# MCU_SCH.net
KiCad netlist of a schematic drawn in Altium Designer
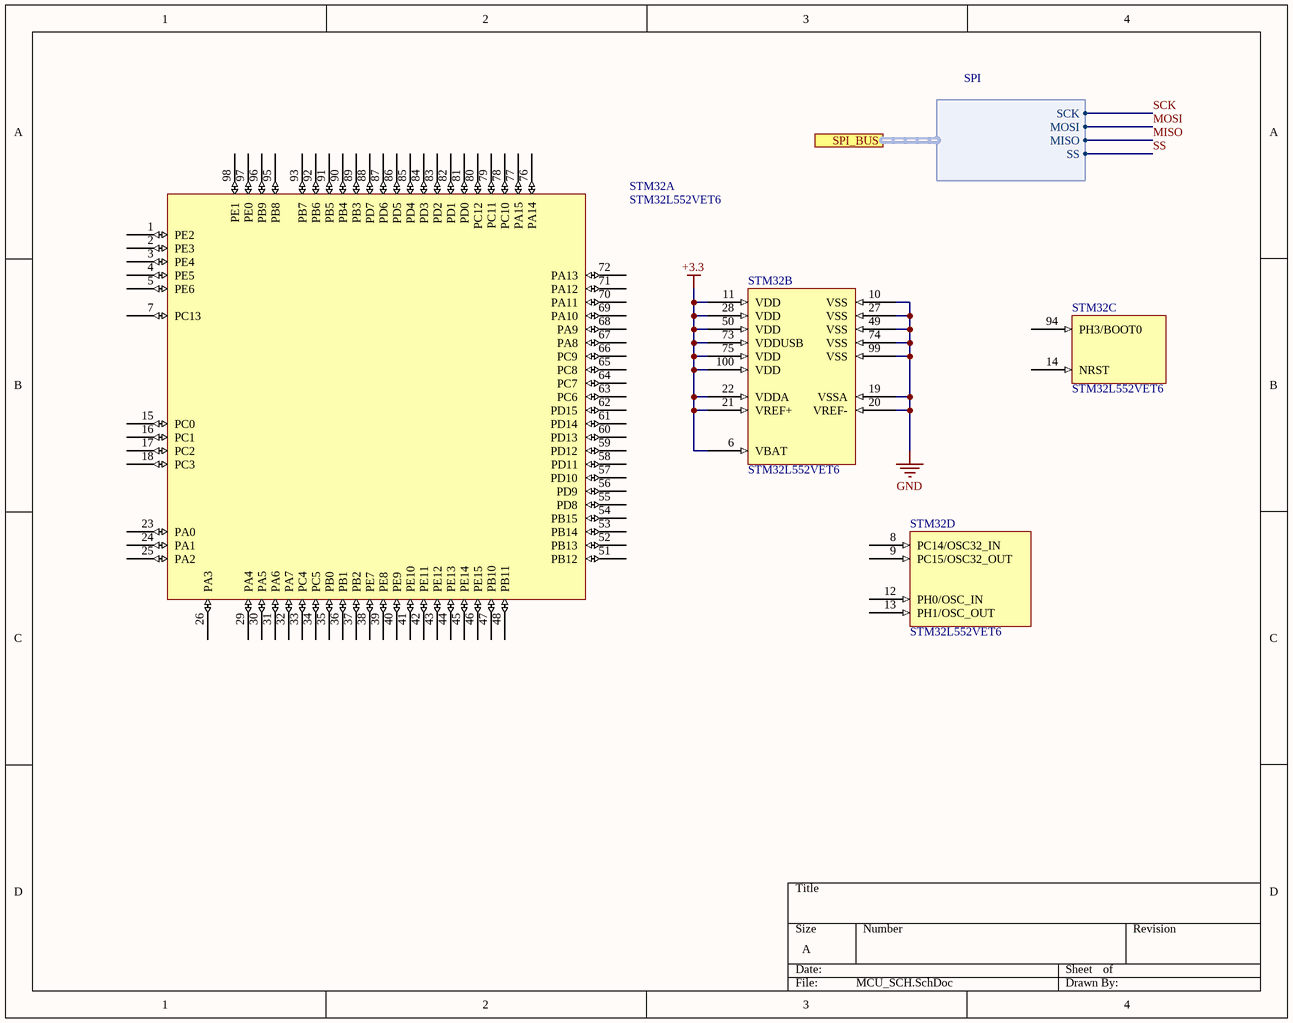
[diagram p0: MCU_SCH.SchDoc]

(export (version "E")
  (design (tool "Eeschema 10.0.6"))
  (components
    (comp (ref "STM32")
      (value "STM32L552VET6")
      (footprint "TSQFP50P1600X1600X160-100N")
      (libsource (lib "University of Minnesota - Solar Vehicle Project") (part "STM32L552VET6-Symbol-1"))
    )
  )
  (nets
    (net (code "2") (name "+3.3") (class "Default")
      (node (ref "STM32") (pin "100") (pinfunction "VDD_100") (pintype "input"))
      (node (ref "STM32") (pin "11") (pinfunction "VDD_11") (pintype "input"))
      (node (ref "STM32") (pin "21") (pinfunction "VREF+_21") (pintype "input"))
      (node (ref "STM32") (pin "22") (pinfunction "VDDA_22") (pintype "input"))
      (node (ref "STM32") (pin "28") (pinfunction "VDD_28") (pintype "input"))
      (node (ref "STM32") (pin "50") (pinfunction "VDD_50") (pintype "input"))
      (node (ref "STM32") (pin "6") (pinfunction "VBAT_6") (pintype "input"))
      (node (ref "STM32") (pin "73") (pinfunction "VDDUSB_73") (pintype "input"))
      (node (ref "STM32") (pin "75") (pinfunction "VDD_75") (pintype "input"))
    )
    (net (code "8") (name "GND") (class "Default")
      (node (ref "STM32") (pin "10") (pinfunction "VSS_10") (pintype "input"))
      (node (ref "STM32") (pin "19") (pinfunction "VSSA_19") (pintype "input"))
      (node (ref "STM32") (pin "20") (pinfunction "VREF-_20") (pintype "input"))
      (node (ref "STM32") (pin "27") (pinfunction "VSS_27") (pintype "input"))
      (node (ref "STM32") (pin "49") (pinfunction "VSS_49") (pintype "input"))
      (node (ref "STM32") (pin "74") (pinfunction "VSS_74") (pintype "input"))
      (node (ref "STM32") (pin "99") (pinfunction "VSS_99") (pintype "input"))
    )
    (net (code "9") (name "unconnected-(STM32A-PA0-Pad23)") (class "Default")
      (node (ref "STM32") (pin "23") (pinfunction "PA0_23") (pintype "bidirectional"))
    )
    (net (code "10") (name "unconnected-(STM32A-PA1-Pad24)") (class "Default")
      (node (ref "STM32") (pin "24") (pinfunction "PA1_24") (pintype "bidirectional"))
    )
    (net (code "11") (name "unconnected-(STM32A-PA2-Pad25)") (class "Default")
      (node (ref "STM32") (pin "25") (pinfunction "PA2_25") (pintype "bidirectional"))
    )
    (net (code "12") (name "unconnected-(STM32A-PA3-Pad26)") (class "Default")
      (node (ref "STM32") (pin "26") (pinfunction "PA3_26") (pintype "bidirectional"))
    )
    (net (code "13") (name "unconnected-(STM32A-PA4-Pad29)") (class "Default")
      (node (ref "STM32") (pin "29") (pinfunction "PA4_29") (pintype "bidirectional"))
    )
    (net (code "14") (name "unconnected-(STM32A-PA5-Pad30)") (class "Default")
      (node (ref "STM32") (pin "30") (pinfunction "PA5_30") (pintype "bidirectional"))
    )
    (net (code "15") (name "unconnected-(STM32A-PA6-Pad31)") (class "Default")
      (node (ref "STM32") (pin "31") (pinfunction "PA6_31") (pintype "bidirectional"))
    )
    (net (code "16") (name "unconnected-(STM32A-PA7-Pad32)") (class "Default")
      (node (ref "STM32") (pin "32") (pinfunction "PA7_32") (pintype "bidirectional"))
    )
    (net (code "17") (name "unconnected-(STM32A-PA8-Pad67)") (class "Default")
      (node (ref "STM32") (pin "67") (pinfunction "PA8_67") (pintype "bidirectional"))
    )
    (net (code "18") (name "unconnected-(STM32A-PA9-Pad68)") (class "Default")
      (node (ref "STM32") (pin "68") (pinfunction "PA9_68") (pintype "bidirectional"))
    )
    (net (code "19") (name "unconnected-(STM32A-PA10-Pad69)") (class "Default")
      (node (ref "STM32") (pin "69") (pinfunction "PA10_69") (pintype "bidirectional"))
    )
    (net (code "20") (name "unconnected-(STM32A-PA11-Pad70)") (class "Default")
      (node (ref "STM32") (pin "70") (pinfunction "PA11_70") (pintype "bidirectional"))
    )
    (net (code "21") (name "unconnected-(STM32A-PA12-Pad71)") (class "Default")
      (node (ref "STM32") (pin "71") (pinfunction "PA12_71") (pintype "bidirectional"))
    )
    (net (code "22") (name "unconnected-(STM32A-PA13-Pad72)") (class "Default")
      (node (ref "STM32") (pin "72") (pinfunction "PA13_72") (pintype "bidirectional"))
    )
    (net (code "23") (name "unconnected-(STM32A-PA14-Pad76)") (class "Default")
      (node (ref "STM32") (pin "76") (pinfunction "PA14_76") (pintype "bidirectional"))
    )
    (net (code "24") (name "unconnected-(STM32A-PA15-Pad77)") (class "Default")
      (node (ref "STM32") (pin "77") (pinfunction "PA15_77") (pintype "bidirectional"))
    )
    (net (code "25") (name "unconnected-(STM32A-PB0-Pad35)") (class "Default")
      (node (ref "STM32") (pin "35") (pinfunction "PB0_35") (pintype "bidirectional"))
    )
    (net (code "26") (name "unconnected-(STM32A-PB1-Pad36)") (class "Default")
      (node (ref "STM32") (pin "36") (pinfunction "PB1_36") (pintype "bidirectional"))
    )
    (net (code "27") (name "unconnected-(STM32A-PB2-Pad37)") (class "Default")
      (node (ref "STM32") (pin "37") (pinfunction "PB2_37") (pintype "bidirectional"))
    )
    (net (code "28") (name "unconnected-(STM32A-PB3-Pad89)") (class "Default")
      (node (ref "STM32") (pin "89") (pinfunction "PB3_89") (pintype "bidirectional"))
    )
    (net (code "29") (name "unconnected-(STM32A-PB4-Pad90)") (class "Default")
      (node (ref "STM32") (pin "90") (pinfunction "PB4_90") (pintype "bidirectional"))
    )
    (net (code "30") (name "unconnected-(STM32A-PB5-Pad91)") (class "Default")
      (node (ref "STM32") (pin "91") (pinfunction "PB5_91") (pintype "bidirectional"))
    )
    (net (code "31") (name "unconnected-(STM32A-PB6-Pad92)") (class "Default")
      (node (ref "STM32") (pin "92") (pinfunction "PB6_92") (pintype "bidirectional"))
    )
    (net (code "32") (name "unconnected-(STM32A-PB7-Pad93)") (class "Default")
      (node (ref "STM32") (pin "93") (pinfunction "PB7_93") (pintype "bidirectional"))
    )
    (net (code "33") (name "unconnected-(STM32A-PB8-Pad95)") (class "Default")
      (node (ref "STM32") (pin "95") (pinfunction "PB8_95") (pintype "bidirectional"))
    )
    (net (code "34") (name "unconnected-(STM32A-PB9-Pad96)") (class "Default")
      (node (ref "STM32") (pin "96") (pinfunction "PB9_96") (pintype "bidirectional"))
    )
    (net (code "35") (name "unconnected-(STM32A-PB10-Pad47)") (class "Default")
      (node (ref "STM32") (pin "47") (pinfunction "PB10_47") (pintype "bidirectional"))
    )
    (net (code "36") (name "unconnected-(STM32A-PB11-Pad48)") (class "Default")
      (node (ref "STM32") (pin "48") (pinfunction "PB11_48") (pintype "bidirectional"))
    )
    (net (code "37") (name "unconnected-(STM32A-PB12-Pad51)") (class "Default")
      (node (ref "STM32") (pin "51") (pinfunction "PB12_51") (pintype "bidirectional"))
    )
    (net (code "38") (name "unconnected-(STM32A-PB13-Pad52)") (class "Default")
      (node (ref "STM32") (pin "52") (pinfunction "PB13_52") (pintype "bidirectional"))
    )
    (net (code "39") (name "unconnected-(STM32A-PB14-Pad53)") (class "Default")
      (node (ref "STM32") (pin "53") (pinfunction "PB14_53") (pintype "bidirectional"))
    )
    (net (code "40") (name "unconnected-(STM32A-PB15-Pad54)") (class "Default")
      (node (ref "STM32") (pin "54") (pinfunction "PB15_54") (pintype "bidirectional"))
    )
    (net (code "41") (name "unconnected-(STM32A-PC0-Pad15)") (class "Default")
      (node (ref "STM32") (pin "15") (pinfunction "PC0_15") (pintype "bidirectional"))
    )
    (net (code "42") (name "unconnected-(STM32A-PC1-Pad16)") (class "Default")
      (node (ref "STM32") (pin "16") (pinfunction "PC1_16") (pintype "bidirectional"))
    )
    (net (code "43") (name "unconnected-(STM32A-PC2-Pad17)") (class "Default")
      (node (ref "STM32") (pin "17") (pinfunction "PC2_17") (pintype "bidirectional"))
    )
    (net (code "44") (name "unconnected-(STM32A-PC3-Pad18)") (class "Default")
      (node (ref "STM32") (pin "18") (pinfunction "PC3_18") (pintype "bidirectional"))
    )
    (net (code "45") (name "unconnected-(STM32A-PC4-Pad33)") (class "Default")
      (node (ref "STM32") (pin "33") (pinfunction "PC4_33") (pintype "bidirectional"))
    )
    (net (code "46") (name "unconnected-(STM32A-PC5-Pad34)") (class "Default")
      (node (ref "STM32") (pin "34") (pinfunction "PC5_34") (pintype "bidirectional"))
    )
    (net (code "47") (name "unconnected-(STM32A-PC6-Pad63)") (class "Default")
      (node (ref "STM32") (pin "63") (pinfunction "PC6_63") (pintype "bidirectional"))
    )
    (net (code "48") (name "unconnected-(STM32A-PC7-Pad64)") (class "Default")
      (node (ref "STM32") (pin "64") (pinfunction "PC7_64") (pintype "bidirectional"))
    )
    (net (code "49") (name "unconnected-(STM32A-PC8-Pad65)") (class "Default")
      (node (ref "STM32") (pin "65") (pinfunction "PC8_65") (pintype "bidirectional"))
    )
    (net (code "50") (name "unconnected-(STM32A-PC9-Pad66)") (class "Default")
      (node (ref "STM32") (pin "66") (pinfunction "PC9_66") (pintype "bidirectional"))
    )
    (net (code "51") (name "unconnected-(STM32A-PC10-Pad78)") (class "Default")
      (node (ref "STM32") (pin "78") (pinfunction "PC10_78") (pintype "bidirectional"))
    )
    (net (code "52") (name "unconnected-(STM32A-PC11-Pad79)") (class "Default")
      (node (ref "STM32") (pin "79") (pinfunction "PC11_79") (pintype "bidirectional"))
    )
    (net (code "53") (name "unconnected-(STM32A-PC12-Pad80)") (class "Default")
      (node (ref "STM32") (pin "80") (pinfunction "PC12_80") (pintype "bidirectional"))
    )
    (net (code "54") (name "unconnected-(STM32A-PC13-Pad7)") (class "Default")
      (node (ref "STM32") (pin "7") (pinfunction "PC13_7") (pintype "bidirectional"))
    )
    (net (code "55") (name "unconnected-(STM32A-PD0-Pad81)") (class "Default")
      (node (ref "STM32") (pin "81") (pinfunction "PD0_81") (pintype "bidirectional"))
    )
    (net (code "56") (name "unconnected-(STM32A-PD1-Pad82)") (class "Default")
      (node (ref "STM32") (pin "82") (pinfunction "PD1_82") (pintype "bidirectional"))
    )
    (net (code "57") (name "unconnected-(STM32A-PD2-Pad83)") (class "Default")
      (node (ref "STM32") (pin "83") (pinfunction "PD2_83") (pintype "bidirectional"))
    )
    (net (code "58") (name "unconnected-(STM32A-PD3-Pad84)") (class "Default")
      (node (ref "STM32") (pin "84") (pinfunction "PD3_84") (pintype "bidirectional"))
    )
    (net (code "59") (name "unconnected-(STM32A-PD4-Pad85)") (class "Default")
      (node (ref "STM32") (pin "85") (pinfunction "PD4_85") (pintype "bidirectional"))
    )
    (net (code "60") (name "unconnected-(STM32A-PD5-Pad86)") (class "Default")
      (node (ref "STM32") (pin "86") (pinfunction "PD5_86") (pintype "bidirectional"))
    )
    (net (code "61") (name "unconnected-(STM32A-PD6-Pad87)") (class "Default")
      (node (ref "STM32") (pin "87") (pinfunction "PD6_87") (pintype "bidirectional"))
    )
    (net (code "62") (name "unconnected-(STM32A-PD7-Pad88)") (class "Default")
      (node (ref "STM32") (pin "88") (pinfunction "PD7_88") (pintype "bidirectional"))
    )
    (net (code "63") (name "unconnected-(STM32A-PD8-Pad55)") (class "Default")
      (node (ref "STM32") (pin "55") (pinfunction "PD8_55") (pintype "bidirectional"))
    )
    (net (code "64") (name "unconnected-(STM32A-PD9-Pad56)") (class "Default")
      (node (ref "STM32") (pin "56") (pinfunction "PD9_56") (pintype "bidirectional"))
    )
    (net (code "65") (name "unconnected-(STM32A-PD10-Pad57)") (class "Default")
      (node (ref "STM32") (pin "57") (pinfunction "PD10_57") (pintype "bidirectional"))
    )
    (net (code "66") (name "unconnected-(STM32A-PD11-Pad58)") (class "Default")
      (node (ref "STM32") (pin "58") (pinfunction "PD11_58") (pintype "bidirectional"))
    )
    (net (code "67") (name "unconnected-(STM32A-PD12-Pad59)") (class "Default")
      (node (ref "STM32") (pin "59") (pinfunction "PD12_59") (pintype "bidirectional"))
    )
    (net (code "68") (name "unconnected-(STM32A-PD13-Pad60)") (class "Default")
      (node (ref "STM32") (pin "60") (pinfunction "PD13_60") (pintype "bidirectional"))
    )
    (net (code "69") (name "unconnected-(STM32A-PD14-Pad61)") (class "Default")
      (node (ref "STM32") (pin "61") (pinfunction "PD14_61") (pintype "bidirectional"))
    )
    (net (code "70") (name "unconnected-(STM32A-PD15-Pad62)") (class "Default")
      (node (ref "STM32") (pin "62") (pinfunction "PD15_62") (pintype "bidirectional"))
    )
    (net (code "71") (name "unconnected-(STM32A-PE0-Pad97)") (class "Default")
      (node (ref "STM32") (pin "97") (pinfunction "PE0_97") (pintype "bidirectional"))
    )
    (net (code "72") (name "unconnected-(STM32A-PE1-Pad98)") (class "Default")
      (node (ref "STM32") (pin "98") (pinfunction "PE1_98") (pintype "bidirectional"))
    )
    (net (code "73") (name "unconnected-(STM32A-PE2-Pad1)") (class "Default")
      (node (ref "STM32") (pin "1") (pinfunction "PE2_1") (pintype "bidirectional"))
    )
    (net (code "74") (name "unconnected-(STM32A-PE3-Pad2)") (class "Default")
      (node (ref "STM32") (pin "2") (pinfunction "PE3_2") (pintype "bidirectional"))
    )
    (net (code "75") (name "unconnected-(STM32A-PE4-Pad3)") (class "Default")
      (node (ref "STM32") (pin "3") (pinfunction "PE4_3") (pintype "bidirectional"))
    )
    (net (code "76") (name "unconnected-(STM32A-PE5-Pad4)") (class "Default")
      (node (ref "STM32") (pin "4") (pinfunction "PE5_4") (pintype "bidirectional"))
    )
    (net (code "77") (name "unconnected-(STM32A-PE6-Pad5)") (class "Default")
      (node (ref "STM32") (pin "5") (pinfunction "PE6_5") (pintype "bidirectional"))
    )
    (net (code "78") (name "unconnected-(STM32A-PE7-Pad38)") (class "Default")
      (node (ref "STM32") (pin "38") (pinfunction "PE7_38") (pintype "bidirectional"))
    )
    (net (code "79") (name "unconnected-(STM32A-PE8-Pad39)") (class "Default")
      (node (ref "STM32") (pin "39") (pinfunction "PE8_39") (pintype "bidirectional"))
    )
    (net (code "80") (name "unconnected-(STM32A-PE9-Pad40)") (class "Default")
      (node (ref "STM32") (pin "40") (pinfunction "PE9_40") (pintype "bidirectional"))
    )
    (net (code "81") (name "unconnected-(STM32A-PE10-Pad41)") (class "Default")
      (node (ref "STM32") (pin "41") (pinfunction "PE10_41") (pintype "bidirectional"))
    )
    (net (code "82") (name "unconnected-(STM32A-PE11-Pad42)") (class "Default")
      (node (ref "STM32") (pin "42") (pinfunction "PE11_42") (pintype "bidirectional"))
    )
    (net (code "83") (name "unconnected-(STM32A-PE12-Pad43)") (class "Default")
      (node (ref "STM32") (pin "43") (pinfunction "PE12_43") (pintype "bidirectional"))
    )
    (net (code "84") (name "unconnected-(STM32A-PE13-Pad44)") (class "Default")
      (node (ref "STM32") (pin "44") (pinfunction "PE13_44") (pintype "bidirectional"))
    )
    (net (code "85") (name "unconnected-(STM32A-PE14-Pad45)") (class "Default")
      (node (ref "STM32") (pin "45") (pinfunction "PE14_45") (pintype "bidirectional"))
    )
    (net (code "86") (name "unconnected-(STM32A-PE15-Pad46)") (class "Default")
      (node (ref "STM32") (pin "46") (pinfunction "PE15_46") (pintype "bidirectional"))
    )
    (net (code "87") (name "unconnected-(STM32C-NRST-Pad14)") (class "Default")
      (node (ref "STM32") (pin "14") (pinfunction "NRST_14") (pintype "input"))
    )
    (net (code "88") (name "unconnected-(STM32C-PH3{slash}BOOT0-Pad94)") (class "Default")
      (node (ref "STM32") (pin "94") (pinfunction "PH3/BOOT0_94") (pintype "input"))
    )
    (net (code "89") (name "unconnected-(STM32D-PC14{slash}OSC32_IN-Pad8)") (class "Default")
      (node (ref "STM32") (pin "8") (pinfunction "PC14/OSC32_IN_8") (pintype "input"))
    )
    (net (code "90") (name "unconnected-(STM32D-PC15{slash}OSC32_OUT-Pad9)") (class "Default")
      (node (ref "STM32") (pin "9") (pinfunction "PC15/OSC32_OUT_9") (pintype "input"))
    )
    (net (code "91") (name "unconnected-(STM32D-PH0{slash}OSC_IN-Pad12)") (class "Default")
      (node (ref "STM32") (pin "12") (pinfunction "PH0/OSC_IN_12") (pintype "input"))
    )
    (net (code "92") (name "unconnected-(STM32D-PH1{slash}OSC_OUT-Pad13)") (class "Default")
      (node (ref "STM32") (pin "13") (pinfunction "PH1/OSC_OUT_13") (pintype "input"))
    )
  )
)
